# SolenoidSwitcher.net
KiCad netlist of a schematic drawn in EAGLE
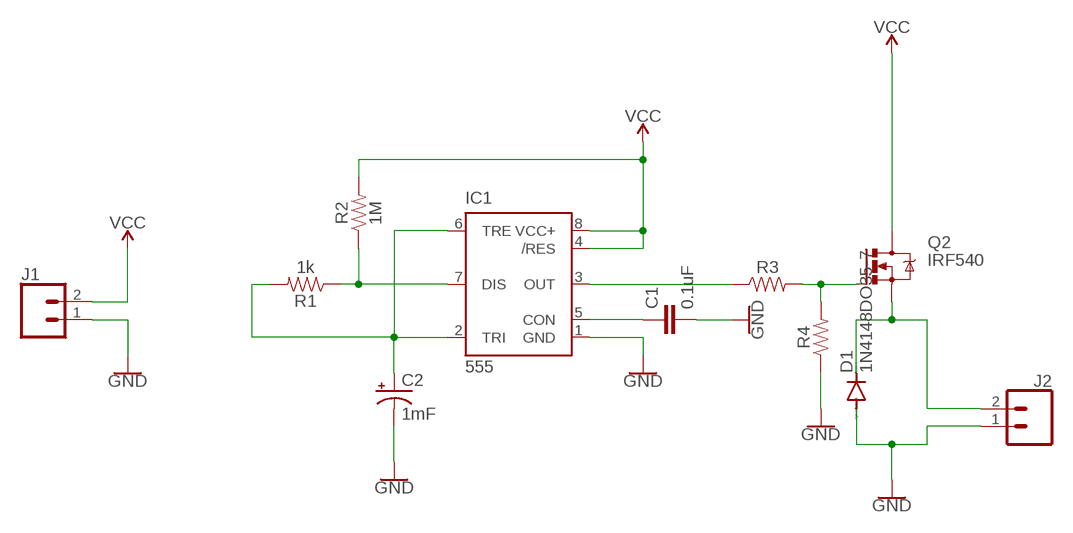
[diagram p0: schematic, sheet 1]

(export (version "E")
  (design (tool "Eeschema 10.0.6"))
  (components
    (comp (ref "C1")
      (value "0.1uF")
      (footprint "eagle-import:CAP-PTH-SMALL-KIT")
      (libsource (lib "eagle-import") (part "0.1UF-KIT-EZ-50V-20%"))
    )
    (comp (ref "C2")
      (value "1mF")
      (footprint "eagle-import:CPOL-RADIAL-5MM-10MM")
      (libsource (lib "eagle-import") (part "1000UF-RADIAL-5MM-25V-20%"))
    )
    (comp (ref "D1")
      (value "1N4148DO35-7")
      (footprint "eagle-import:DO35-7")
      (libsource (lib "eagle-import") (part "1N4148DO35-7"))
    )
    (comp (ref "IC1")
      (value "555")
      (footprint "eagle-import:DIP08")
      (libsource (lib "eagle-import") (part "555P"))
    )
    (comp (ref "J1")
      (value "CONN_02")
      (footprint "eagle-import:1X02")
      (libsource (lib "eagle-import") (part "CONN_02"))
    )
    (comp (ref "J2")
      (value "CONN_02")
      (footprint "eagle-import:1X02")
      (libsource (lib "eagle-import") (part "CONN_02"))
    )
    (comp (ref "Q2")
      (value "IRF540")
      (footprint "eagle-import:TO220BV")
      (libsource (lib "eagle-import") (part "IRF540"))
    )
    (comp (ref "R1")
      (value "1k")
      (footprint "eagle-import:AXIAL-0.1")
      (libsource (lib "eagle-import") (part "1KOHM-VERT-1/4W-1%"))
    )
    (comp (ref "R2")
      (value "1M")
      (footprint "eagle-import:AXIAL-0.1")
      (libsource (lib "eagle-import") (part "1MOHM-VERT-1/4W-5%"))
    )
    (comp (ref "R3")
      (value "RESISTORAXIAL-0.3")
      (footprint "eagle-import:AXIAL-0.3")
      (libsource (lib "eagle-import") (part "RESISTORAXIAL-0.3"))
    )
    (comp (ref "R4")
      (value "RESISTORAXIAL-0.3")
      (footprint "eagle-import:AXIAL-0.3")
      (libsource (lib "eagle-import") (part "RESISTORAXIAL-0.3"))
    )
  )
  (nets
    (net (code "1") (name "GND") (class "Default")
      (node (ref "C1") (pin "2") (pinfunction "2_2") (pintype "passive"))
      (node (ref "C2") (pin "-") (pinfunction "-_-") (pintype "passive"))
      (node (ref "D1") (pin "A") (pinfunction "A_A") (pintype "passive"))
      (node (ref "IC1") (pin "1") (pinfunction "GND_1") (pintype "power_in"))
      (node (ref "J1") (pin "1") (pinfunction "1_1") (pintype "passive"))
      (node (ref "J2") (pin "1") (pinfunction "1_1") (pintype "passive"))
      (node (ref "R4") (pin "P$1") (pinfunction "1_P$1") (pintype "passive"))
    )
    (net (code "2") (name "Net-(D1-PadC)") (class "Default")
      (node (ref "D1") (pin "C") (pinfunction "C_C") (pintype "passive"))
      (node (ref "J2") (pin "2") (pinfunction "2_2") (pintype "passive"))
      (node (ref "Q2") (pin "S") (pinfunction "S_S") (pintype "passive"))
    )
    (net (code "3") (name "Net-(IC1-CON)") (class "Default")
      (node (ref "C1") (pin "1") (pinfunction "1_1") (pintype "passive"))
      (node (ref "IC1") (pin "5") (pinfunction "CON_5") (pintype "input"))
    )
    (net (code "4") (name "Net-(IC1-DIS)") (class "Default")
      (node (ref "IC1") (pin "7") (pinfunction "DIS_7") (pintype "input"))
      (node (ref "R1") (pin "P$1") (pinfunction "1_P$1") (pintype "passive"))
      (node (ref "R2") (pin "P$1") (pinfunction "1_P$1") (pintype "passive"))
    )
    (net (code "5") (name "Net-(IC1-OUT)") (class "Default")
      (node (ref "IC1") (pin "3") (pinfunction "OUT_3") (pintype "output"))
      (node (ref "R3") (pin "P$1") (pinfunction "1_P$1") (pintype "passive"))
    )
    (net (code "6") (name "Net-(IC1-TRE)") (class "Default")
      (node (ref "C2") (pin "+") (pinfunction "+_+") (pintype "passive"))
      (node (ref "IC1") (pin "2") (pinfunction "TRI_2") (pintype "input"))
      (node (ref "IC1") (pin "6") (pinfunction "TRE_6") (pintype "input"))
      (node (ref "R1") (pin "P$2") (pinfunction "2_P$2") (pintype "passive"))
    )
    (net (code "7") (name "Net-(R3-2)") (class "Default")
      (node (ref "Q2") (pin "G") (pinfunction "G_G") (pintype "passive"))
      (node (ref "R3") (pin "P$2") (pinfunction "2_P$2") (pintype "passive"))
      (node (ref "R4") (pin "P$2") (pinfunction "2_P$2") (pintype "passive"))
    )
    (net (code "8") (name "VCC") (class "Default")
      (node (ref "IC1") (pin "4") (pinfunction "/RES_4") (pintype "input"))
      (node (ref "IC1") (pin "8") (pinfunction "VCC+_8") (pintype "power_in"))
      (node (ref "J1") (pin "2") (pinfunction "2_2") (pintype "passive"))
      (node (ref "Q2") (pin "D") (pinfunction "D_D") (pintype "passive"))
      (node (ref "R2") (pin "P$2") (pinfunction "2_P$2") (pintype "passive"))
    )
  )
)
